# kaaEmonitor_2v0.net
KiCad netlist of a schematic drawn in EAGLE
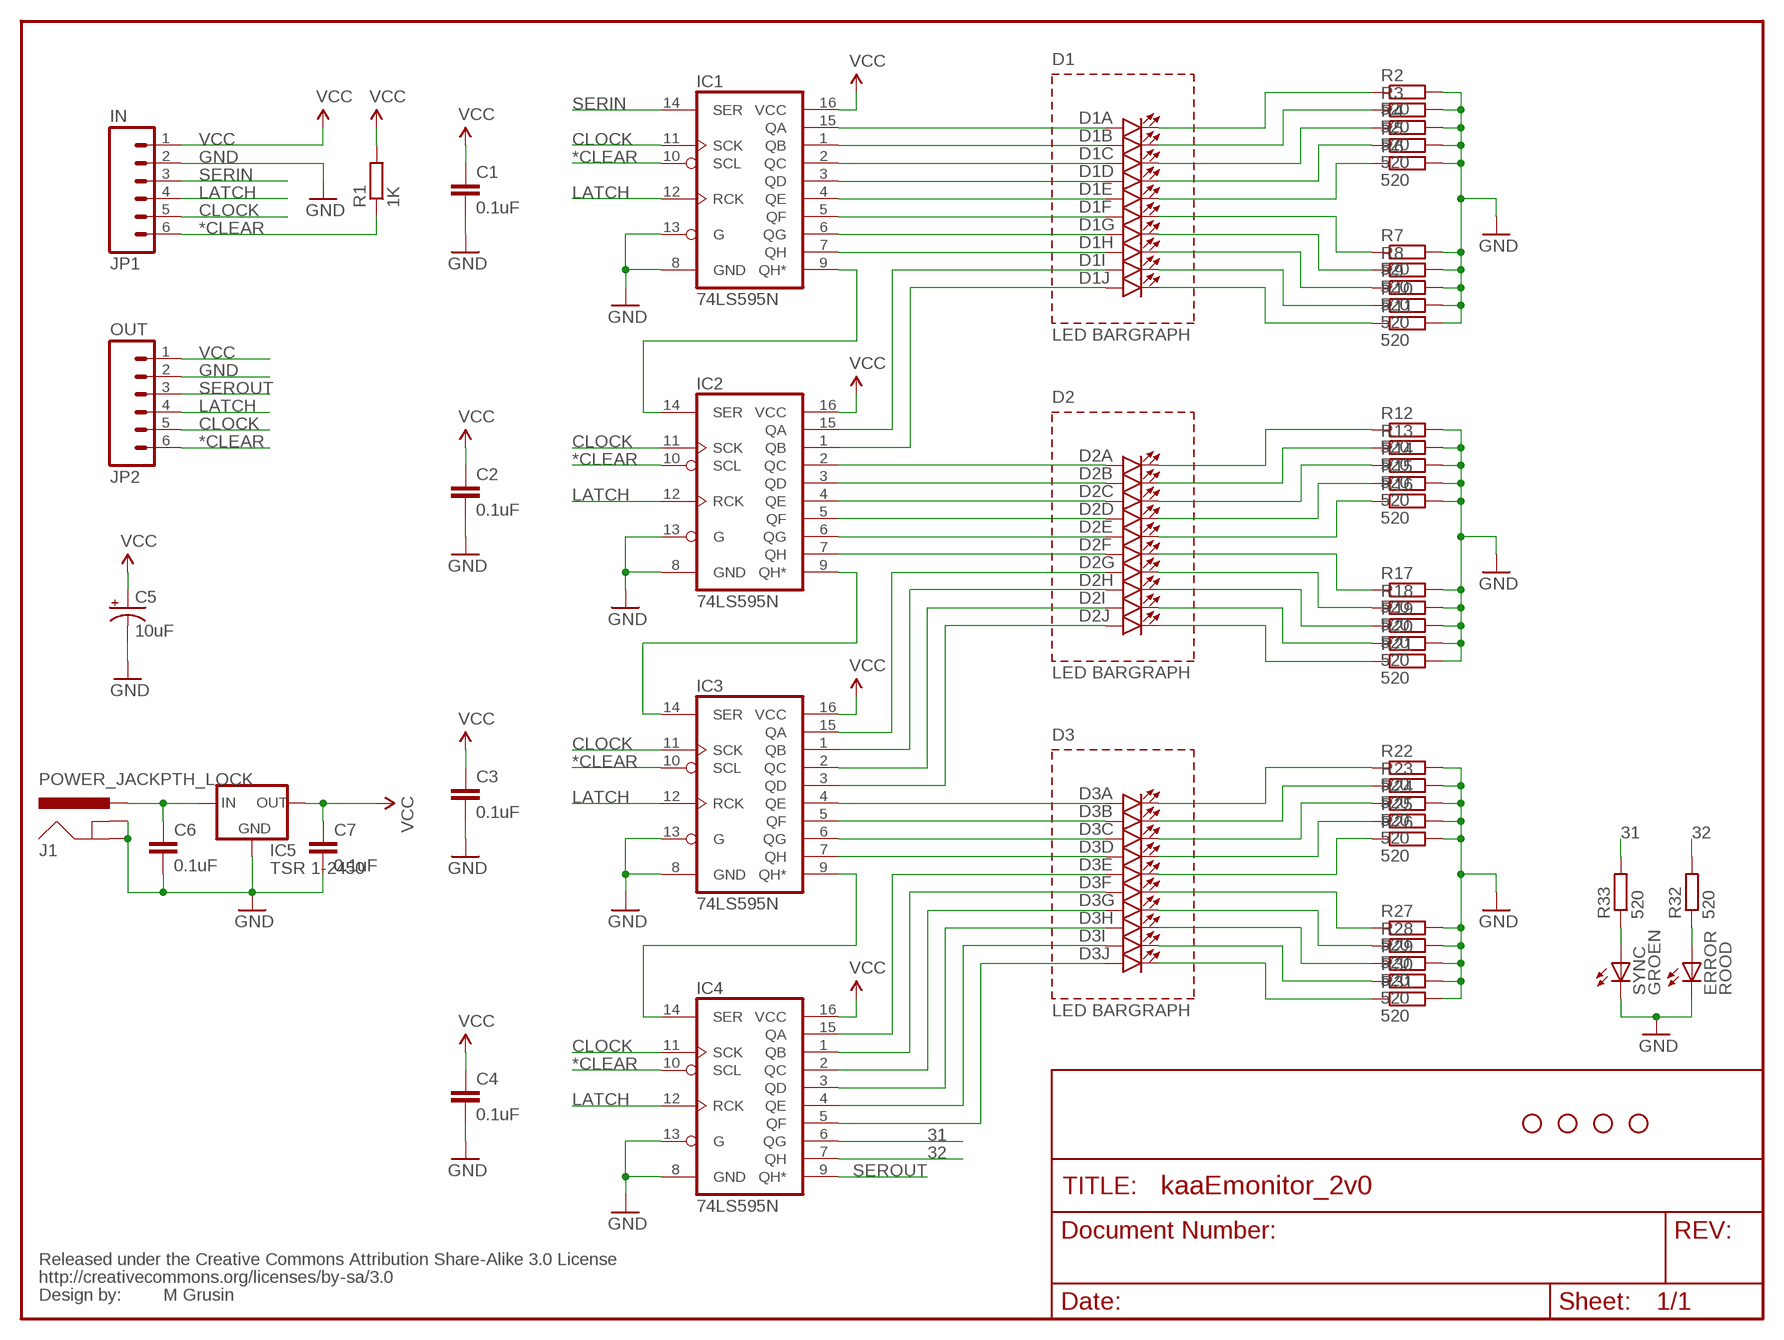
[diagram p0: schematic, sheet 1]

(export (version "E")
  (design (tool "Eeschema 10.0.6"))
  (components
    (comp (ref "C1")
      (value "0.1uF")
      (footprint "eagle-import:CAP-PTH-SMALL2")
      (libsource (lib "eagle-import") (part "CAPPTH2"))
    )
    (comp (ref "C2")
      (value "0.1uF")
      (footprint "eagle-import:CAP-PTH-SMALL2")
      (libsource (lib "eagle-import") (part "CAPPTH2"))
    )
    (comp (ref "C3")
      (value "0.1uF")
      (footprint "eagle-import:CAP-PTH-SMALL2")
      (libsource (lib "eagle-import") (part "CAPPTH2"))
    )
    (comp (ref "C4")
      (value "0.1uF")
      (footprint "eagle-import:CAP-PTH-SMALL2")
      (libsource (lib "eagle-import") (part "CAPPTH2"))
    )
    (comp (ref "C5")
      (value "10uF")
      (footprint "eagle-import:CPOL-RADIAL-10UF-25V")
      (libsource (lib "eagle-import") (part "CAP_POLPTH2"))
    )
    (comp (ref "C6")
      (value "0.1uF")
      (footprint "eagle-import:CAP-PTH-SMALL2")
      (libsource (lib "eagle-import") (part "CAPPTH2"))
    )
    (comp (ref "C7")
      (value "0.1uF")
      (footprint "eagle-import:CAP-PTH-SMALL2")
      (libsource (lib "eagle-import") (part "CAPPTH2"))
    )
    (comp (ref "D1")
      (value "LED_BARGRAPH_10")
      (footprint "eagle-import:LED_BARGAPH_10")
      (libsource (lib "eagle-import") (part "LED_BARGRAPH_10"))
    )
    (comp (ref "D2")
      (value "LED_BARGRAPH_10")
      (footprint "eagle-import:LED_BARGAPH_10")
      (libsource (lib "eagle-import") (part "LED_BARGRAPH_10"))
    )
    (comp (ref "D3")
      (value "LED_BARGRAPH_10")
      (footprint "eagle-import:LED_BARGAPH_10")
      (libsource (lib "eagle-import") (part "LED_BARGRAPH_10"))
    )
    (comp (ref "ERROR")
      (value "ROOD")
      (footprint "eagle-import:LED3MM")
      (libsource (lib "eagle-import") (part "LED3MM"))
    )
    (comp (ref "IC1")
      (value "74LS595N")
      (footprint "eagle-import:DIL16")
      (libsource (lib "eagle-import") (part "74595NLS"))
    )
    (comp (ref "IC2")
      (value "74LS595N")
      (footprint "eagle-import:DIL16")
      (libsource (lib "eagle-import") (part "74595NLS"))
    )
    (comp (ref "IC3")
      (value "74LS595N")
      (footprint "eagle-import:DIL16")
      (libsource (lib "eagle-import") (part "74595NLS"))
    )
    (comp (ref "IC4")
      (value "74LS595N")
      (footprint "eagle-import:DIL16")
      (libsource (lib "eagle-import") (part "74595NLS"))
    )
    (comp (ref "IC5")
      (value "TSR 1-2450")
      (footprint "eagle-import:TO220-IGO")
      (libsource (lib "eagle-import") (part "V_REG_78XXSINK"))
    )
    (comp (ref "J1")
      (value "POWER_JACKPTH_LOCK")
      (footprint "eagle-import:POWER_JACK_PTH_LOCK")
      (libsource (lib "eagle-import") (part "POWER_JACKPTH_LOCK"))
    )
    (comp (ref "JP1")
      (value "IN")
      (footprint "eagle-import:1X06")
      (libsource (lib "eagle-import") (part "M06SIP"))
    )
    (comp (ref "JP2")
      (value "OUT")
      (footprint "eagle-import:1X06")
      (libsource (lib "eagle-import") (part "M06SIP"))
    )
    (comp (ref "R1")
      (value "1K")
      (footprint "eagle-import:0204_5")
      (libsource (lib "eagle-import") (part "R-EU_0204/5"))
    )
    (comp (ref "R2")
      (value "520")
      (footprint "eagle-import:0204_5")
      (libsource (lib "eagle-import") (part "R-EU_0204/5"))
    )
    (comp (ref "R3")
      (value "520")
      (footprint "eagle-import:0204_5")
      (libsource (lib "eagle-import") (part "R-EU_0204/5"))
    )
    (comp (ref "R4")
      (value "520")
      (footprint "eagle-import:0204_5")
      (libsource (lib "eagle-import") (part "R-EU_0204/5"))
    )
    (comp (ref "R5")
      (value "520")
      (footprint "eagle-import:0204_5")
      (libsource (lib "eagle-import") (part "R-EU_0204/5"))
    )
    (comp (ref "R6")
      (value "520")
      (footprint "eagle-import:0204_5")
      (libsource (lib "eagle-import") (part "R-EU_0204/5"))
    )
    (comp (ref "R7")
      (value "520")
      (footprint "eagle-import:0204_5")
      (libsource (lib "eagle-import") (part "R-EU_0204/5"))
    )
    (comp (ref "R8")
      (value "520")
      (footprint "eagle-import:0204_5")
      (libsource (lib "eagle-import") (part "R-EU_0204/5"))
    )
    (comp (ref "R9")
      (value "520")
      (footprint "eagle-import:0204_5")
      (libsource (lib "eagle-import") (part "R-EU_0204/5"))
    )
    (comp (ref "R10")
      (value "520")
      (footprint "eagle-import:0204_5")
      (libsource (lib "eagle-import") (part "R-EU_0204/5"))
    )
    (comp (ref "R11")
      (value "520")
      (footprint "eagle-import:0204_5")
      (libsource (lib "eagle-import") (part "R-EU_0204/5"))
    )
    (comp (ref "R12")
      (value "520")
      (footprint "eagle-import:0204_5")
      (libsource (lib "eagle-import") (part "R-EU_0204/5"))
    )
    (comp (ref "R13")
      (value "520")
      (footprint "eagle-import:0204_5")
      (libsource (lib "eagle-import") (part "R-EU_0204/5"))
    )
    (comp (ref "R14")
      (value "520")
      (footprint "eagle-import:0204_5")
      (libsource (lib "eagle-import") (part "R-EU_0204/5"))
    )
    (comp (ref "R15")
      (value "520")
      (footprint "eagle-import:0204_5")
      (libsource (lib "eagle-import") (part "R-EU_0204/5"))
    )
    (comp (ref "R16")
      (value "520")
      (footprint "eagle-import:0204_5")
      (libsource (lib "eagle-import") (part "R-EU_0204/5"))
    )
    (comp (ref "R17")
      (value "520")
      (footprint "eagle-import:0204_5")
      (libsource (lib "eagle-import") (part "R-EU_0204/5"))
    )
    (comp (ref "R18")
      (value "520")
      (footprint "eagle-import:0204_5")
      (libsource (lib "eagle-import") (part "R-EU_0204/5"))
    )
    (comp (ref "R19")
      (value "520")
      (footprint "eagle-import:0204_5")
      (libsource (lib "eagle-import") (part "R-EU_0204/5"))
    )
    (comp (ref "R20")
      (value "520")
      (footprint "eagle-import:0204_5")
      (libsource (lib "eagle-import") (part "R-EU_0204/5"))
    )
    (comp (ref "R21")
      (value "520")
      (footprint "eagle-import:0204_5")
      (libsource (lib "eagle-import") (part "R-EU_0204/5"))
    )
    (comp (ref "R22")
      (value "520")
      (footprint "eagle-import:0204_5")
      (libsource (lib "eagle-import") (part "R-EU_0204/5"))
    )
    (comp (ref "R23")
      (value "520")
      (footprint "eagle-import:0204_5")
      (libsource (lib "eagle-import") (part "R-EU_0204/5"))
    )
    (comp (ref "R24")
      (value "520")
      (footprint "eagle-import:0204_5")
      (libsource (lib "eagle-import") (part "R-EU_0204/5"))
    )
    (comp (ref "R25")
      (value "520")
      (footprint "eagle-import:0204_5")
      (libsource (lib "eagle-import") (part "R-EU_0204/5"))
    )
    (comp (ref "R26")
      (value "520")
      (footprint "eagle-import:0204_5")
      (libsource (lib "eagle-import") (part "R-EU_0204/5"))
    )
    (comp (ref "R27")
      (value "520")
      (footprint "eagle-import:0204_5")
      (libsource (lib "eagle-import") (part "R-EU_0204/5"))
    )
    (comp (ref "R28")
      (value "520")
      (footprint "eagle-import:0204_5")
      (libsource (lib "eagle-import") (part "R-EU_0204/5"))
    )
    (comp (ref "R29")
      (value "520")
      (footprint "eagle-import:0204_5")
      (libsource (lib "eagle-import") (part "R-EU_0204/5"))
    )
    (comp (ref "R30")
      (value "520")
      (footprint "eagle-import:0204_5")
      (libsource (lib "eagle-import") (part "R-EU_0204/5"))
    )
    (comp (ref "R31")
      (value "520")
      (footprint "eagle-import:0204_5")
      (libsource (lib "eagle-import") (part "R-EU_0204/5"))
    )
    (comp (ref "R32")
      (value "520")
      (footprint "eagle-import:0204_5")
      (libsource (lib "eagle-import") (part "R-EU_0204/5"))
    )
    (comp (ref "R33")
      (value "520")
      (footprint "eagle-import:0204_5")
      (libsource (lib "eagle-import") (part "R-EU_0204/5"))
    )
    (comp (ref "SO1")
      (value "STAND-OFF")
      (footprint "eagle-import:STAND-OFF")
      (libsource (lib "eagle-import") (part "STAND-OFF"))
    )
    (comp (ref "SO2")
      (value "STAND-OFF")
      (footprint "eagle-import:STAND-OFF")
      (libsource (lib "eagle-import") (part "STAND-OFF"))
    )
    (comp (ref "SO3")
      (value "STAND-OFF")
      (footprint "eagle-import:STAND-OFF")
      (libsource (lib "eagle-import") (part "STAND-OFF"))
    )
    (comp (ref "SO4")
      (value "STAND-OFF")
      (footprint "eagle-import:STAND-OFF")
      (libsource (lib "eagle-import") (part "STAND-OFF"))
    )
    (comp (ref "SYNC")
      (value "GROEN")
      (footprint "eagle-import:LED3MM")
      (libsource (lib "eagle-import") (part "LED3MM"))
    )
    (comp (ref "U$6")
      (value "CREATIVE_COMMONS")
      (footprint "eagle-import:CREATIVE_COMMONS")
      (libsource (lib "eagle-import") (part "CREATIVE_COMMONS"))
    )
  )
  (nets
    (net (code "1") (name "/*CLEAR") (class "Default")
      (node (ref "IC1") (pin "10") (pinfunction "SCL_10") (pintype "input"))
      (node (ref "IC2") (pin "10") (pinfunction "SCL_10") (pintype "input"))
      (node (ref "IC3") (pin "10") (pinfunction "SCL_10") (pintype "input"))
      (node (ref "IC4") (pin "10") (pinfunction "SCL_10") (pintype "input"))
      (node (ref "JP1") (pin "6") (pinfunction "6_6") (pintype "passive"))
      (node (ref "JP2") (pin "6") (pinfunction "6_6") (pintype "passive"))
      (node (ref "R1") (pin "1") (pinfunction "1_1") (pintype "passive"))
    )
    (net (code "2") (name "/31") (class "Default")
      (node (ref "IC4") (pin "6") (pinfunction "QG_6") (pintype "tri_state"))
      (node (ref "R33") (pin "2") (pinfunction "2_2") (pintype "passive"))
    )
    (net (code "3") (name "/32") (class "Default")
      (node (ref "IC4") (pin "7") (pinfunction "QH_7") (pintype "tri_state"))
      (node (ref "R32") (pin "2") (pinfunction "2_2") (pintype "passive"))
    )
    (net (code "4") (name "/CLOCK") (class "Default")
      (node (ref "IC1") (pin "11") (pinfunction "SCK_11") (pintype "input"))
      (node (ref "IC2") (pin "11") (pinfunction "SCK_11") (pintype "input"))
      (node (ref "IC3") (pin "11") (pinfunction "SCK_11") (pintype "input"))
      (node (ref "IC4") (pin "11") (pinfunction "SCK_11") (pintype "input"))
      (node (ref "JP1") (pin "5") (pinfunction "5_5") (pintype "passive"))
      (node (ref "JP2") (pin "5") (pinfunction "5_5") (pintype "passive"))
    )
    (net (code "5") (name "/LATCH") (class "Default")
      (node (ref "IC1") (pin "12") (pinfunction "RCK_12") (pintype "input"))
      (node (ref "IC2") (pin "12") (pinfunction "RCK_12") (pintype "input"))
      (node (ref "IC3") (pin "12") (pinfunction "RCK_12") (pintype "input"))
      (node (ref "IC4") (pin "12") (pinfunction "RCK_12") (pintype "input"))
      (node (ref "JP1") (pin "4") (pinfunction "4_4") (pintype "passive"))
      (node (ref "JP2") (pin "4") (pinfunction "4_4") (pintype "passive"))
    )
    (net (code "6") (name "/SERIN") (class "Default")
      (node (ref "IC1") (pin "14") (pinfunction "SER_14") (pintype "input"))
      (node (ref "JP1") (pin "3") (pinfunction "3_3") (pintype "passive"))
    )
    (net (code "7") (name "/SEROUT") (class "Default")
      (node (ref "IC4") (pin "9") (pinfunction "QH*_9") (pintype "tri_state"))
      (node (ref "JP2") (pin "3") (pinfunction "3_3") (pintype "passive"))
    )
    (net (code "8") (name "GND") (class "Default")
      (node (ref "C1") (pin "2") (pinfunction "2_2") (pintype "passive"))
      (node (ref "C2") (pin "2") (pinfunction "2_2") (pintype "passive"))
      (node (ref "C3") (pin "2") (pinfunction "2_2") (pintype "passive"))
      (node (ref "C4") (pin "2") (pinfunction "2_2") (pintype "passive"))
      (node (ref "C5") (pin "2") (pinfunction "-_2") (pintype "passive"))
      (node (ref "C6") (pin "2") (pinfunction "2_2") (pintype "passive"))
      (node (ref "C7") (pin "2") (pinfunction "2_2") (pintype "passive"))
      (node (ref "ERROR") (pin "K") (pinfunction "C_K") (pintype "passive"))
      (node (ref "IC1") (pin "13") (pinfunction "G_13") (pintype "input"))
      (node (ref "IC1") (pin "8") (pinfunction "GND_8") (pintype "power_in"))
      (node (ref "IC2") (pin "13") (pinfunction "G_13") (pintype "input"))
      (node (ref "IC2") (pin "8") (pinfunction "GND_8") (pintype "power_in"))
      (node (ref "IC3") (pin "13") (pinfunction "G_13") (pintype "input"))
      (node (ref "IC3") (pin "8") (pinfunction "GND_8") (pintype "power_in"))
      (node (ref "IC4") (pin "13") (pinfunction "G_13") (pintype "input"))
      (node (ref "IC4") (pin "8") (pinfunction "GND_8") (pintype "power_in"))
      (node (ref "IC5") (pin "GND") (pinfunction "GND_GND") (pintype "input"))
      (node (ref "J1") (pin "GND") (pinfunction "GND_GND") (pintype "bidirectional"))
      (node (ref "J1") (pin "GNDBREAK") (pinfunction "GNDBREAK_GNDBREAK") (pintype "bidirectional"))
      (node (ref "JP1") (pin "2") (pinfunction "2_2") (pintype "passive"))
      (node (ref "JP2") (pin "2") (pinfunction "2_2") (pintype "passive"))
      (node (ref "R10") (pin "2") (pinfunction "2_2") (pintype "passive"))
      (node (ref "R11") (pin "2") (pinfunction "2_2") (pintype "passive"))
      (node (ref "R12") (pin "2") (pinfunction "2_2") (pintype "passive"))
      (node (ref "R13") (pin "2") (pinfunction "2_2") (pintype "passive"))
      (node (ref "R14") (pin "2") (pinfunction "2_2") (pintype "passive"))
      (node (ref "R15") (pin "2") (pinfunction "2_2") (pintype "passive"))
      (node (ref "R16") (pin "2") (pinfunction "2_2") (pintype "passive"))
      (node (ref "R17") (pin "2") (pinfunction "2_2") (pintype "passive"))
      (node (ref "R18") (pin "2") (pinfunction "2_2") (pintype "passive"))
      (node (ref "R19") (pin "2") (pinfunction "2_2") (pintype "passive"))
      (node (ref "R2") (pin "2") (pinfunction "2_2") (pintype "passive"))
      (node (ref "R20") (pin "2") (pinfunction "2_2") (pintype "passive"))
      (node (ref "R21") (pin "2") (pinfunction "2_2") (pintype "passive"))
      (node (ref "R22") (pin "2") (pinfunction "2_2") (pintype "passive"))
      (node (ref "R23") (pin "2") (pinfunction "2_2") (pintype "passive"))
      (node (ref "R24") (pin "2") (pinfunction "2_2") (pintype "passive"))
      (node (ref "R25") (pin "2") (pinfunction "2_2") (pintype "passive"))
      (node (ref "R26") (pin "2") (pinfunction "2_2") (pintype "passive"))
      (node (ref "R27") (pin "2") (pinfunction "2_2") (pintype "passive"))
      (node (ref "R28") (pin "2") (pinfunction "2_2") (pintype "passive"))
      (node (ref "R29") (pin "2") (pinfunction "2_2") (pintype "passive"))
      (node (ref "R3") (pin "2") (pinfunction "2_2") (pintype "passive"))
      (node (ref "R30") (pin "2") (pinfunction "2_2") (pintype "passive"))
      (node (ref "R31") (pin "2") (pinfunction "2_2") (pintype "passive"))
      (node (ref "R4") (pin "2") (pinfunction "2_2") (pintype "passive"))
      (node (ref "R5") (pin "2") (pinfunction "2_2") (pintype "passive"))
      (node (ref "R6") (pin "2") (pinfunction "2_2") (pintype "passive"))
      (node (ref "R7") (pin "2") (pinfunction "2_2") (pintype "passive"))
      (node (ref "R8") (pin "2") (pinfunction "2_2") (pintype "passive"))
      (node (ref "R9") (pin "2") (pinfunction "2_2") (pintype "passive"))
      (node (ref "SYNC") (pin "K") (pinfunction "C_K") (pintype "passive"))
    )
    (net (code "9") (name "Net-(C6-Pad1)") (class "Default")
      (node (ref "C6") (pin "1") (pinfunction "1_1") (pintype "passive"))
      (node (ref "IC5") (pin "IN") (pinfunction "IN_IN") (pintype "input"))
      (node (ref "J1") (pin "PWR") (pinfunction "PWR_PWR") (pintype "bidirectional"))
    )
    (net (code "10") (name "Net-(D1A-A)") (class "Default")
      (node (ref "D1") (pin "1") (pinfunction "A_1") (pintype "passive"))
      (node (ref "IC1") (pin "15") (pinfunction "QA_15") (pintype "tri_state"))
    )
    (net (code "11") (name "Net-(D1A-C)") (class "Default")
      (node (ref "D1") (pin "20") (pinfunction "C_20") (pintype "passive"))
      (node (ref "R2") (pin "1") (pinfunction "1_1") (pintype "passive"))
    )
    (net (code "12") (name "Net-(D1B-A)") (class "Default")
      (node (ref "D1") (pin "2") (pinfunction "A_2") (pintype "passive"))
      (node (ref "IC1") (pin "1") (pinfunction "QB_1") (pintype "tri_state"))
    )
    (net (code "13") (name "Net-(D1B-C)") (class "Default")
      (node (ref "D1") (pin "19") (pinfunction "C_19") (pintype "passive"))
      (node (ref "R3") (pin "1") (pinfunction "1_1") (pintype "passive"))
    )
    (net (code "14") (name "Net-(D1C-A)") (class "Default")
      (node (ref "D1") (pin "3") (pinfunction "A_3") (pintype "passive"))
      (node (ref "IC1") (pin "2") (pinfunction "QC_2") (pintype "tri_state"))
    )
    (net (code "15") (name "Net-(D1C-C)") (class "Default")
      (node (ref "D1") (pin "18") (pinfunction "C_18") (pintype "passive"))
      (node (ref "R4") (pin "1") (pinfunction "1_1") (pintype "passive"))
    )
    (net (code "16") (name "Net-(D1D-A)") (class "Default")
      (node (ref "D1") (pin "4") (pinfunction "A_4") (pintype "passive"))
      (node (ref "IC1") (pin "3") (pinfunction "QD_3") (pintype "tri_state"))
    )
    (net (code "17") (name "Net-(D1D-C)") (class "Default")
      (node (ref "D1") (pin "17") (pinfunction "C_17") (pintype "passive"))
      (node (ref "R5") (pin "1") (pinfunction "1_1") (pintype "passive"))
    )
    (net (code "18") (name "Net-(D1E-A)") (class "Default")
      (node (ref "D1") (pin "5") (pinfunction "A_5") (pintype "passive"))
      (node (ref "IC1") (pin "4") (pinfunction "QE_4") (pintype "tri_state"))
    )
    (net (code "19") (name "Net-(D1E-C)") (class "Default")
      (node (ref "D1") (pin "16") (pinfunction "C_16") (pintype "passive"))
      (node (ref "R6") (pin "1") (pinfunction "1_1") (pintype "passive"))
    )
    (net (code "20") (name "Net-(D1F-A)") (class "Default")
      (node (ref "D1") (pin "6") (pinfunction "A_6") (pintype "passive"))
      (node (ref "IC1") (pin "5") (pinfunction "QF_5") (pintype "tri_state"))
    )
    (net (code "21") (name "Net-(D1F-C)") (class "Default")
      (node (ref "D1") (pin "15") (pinfunction "C_15") (pintype "passive"))
      (node (ref "R7") (pin "1") (pinfunction "1_1") (pintype "passive"))
    )
    (net (code "22") (name "Net-(D1G-A)") (class "Default")
      (node (ref "D1") (pin "7") (pinfunction "A_7") (pintype "passive"))
      (node (ref "IC1") (pin "6") (pinfunction "QG_6") (pintype "tri_state"))
    )
    (net (code "23") (name "Net-(D1G-C)") (class "Default")
      (node (ref "D1") (pin "14") (pinfunction "C_14") (pintype "passive"))
      (node (ref "R8") (pin "1") (pinfunction "1_1") (pintype "passive"))
    )
    (net (code "24") (name "Net-(D1H-A)") (class "Default")
      (node (ref "D1") (pin "8") (pinfunction "A_8") (pintype "passive"))
      (node (ref "IC1") (pin "7") (pinfunction "QH_7") (pintype "tri_state"))
    )
    (net (code "25") (name "Net-(D1H-C)") (class "Default")
      (node (ref "D1") (pin "13") (pinfunction "C_13") (pintype "passive"))
      (node (ref "R9") (pin "1") (pinfunction "1_1") (pintype "passive"))
    )
    (net (code "26") (name "Net-(D1I-A)") (class "Default")
      (node (ref "D1") (pin "9") (pinfunction "A_9") (pintype "passive"))
      (node (ref "IC2") (pin "15") (pinfunction "QA_15") (pintype "tri_state"))
    )
    (net (code "27") (name "Net-(D1I-C)") (class "Default")
      (node (ref "D1") (pin "12") (pinfunction "C_12") (pintype "passive"))
      (node (ref "R10") (pin "1") (pinfunction "1_1") (pintype "passive"))
    )
    (net (code "28") (name "Net-(D1J-A)") (class "Default")
      (node (ref "D1") (pin "10") (pinfunction "A_10") (pintype "passive"))
      (node (ref "IC2") (pin "1") (pinfunction "QB_1") (pintype "tri_state"))
    )
    (net (code "29") (name "Net-(D1J-C)") (class "Default")
      (node (ref "D1") (pin "11") (pinfunction "C_11") (pintype "passive"))
      (node (ref "R11") (pin "1") (pinfunction "1_1") (pintype "passive"))
    )
    (net (code "30") (name "Net-(D2A-A)") (class "Default")
      (node (ref "D2") (pin "1") (pinfunction "A_1") (pintype "passive"))
      (node (ref "IC2") (pin "2") (pinfunction "QC_2") (pintype "tri_state"))
    )
    (net (code "31") (name "Net-(D2A-C)") (class "Default")
      (node (ref "D2") (pin "20") (pinfunction "C_20") (pintype "passive"))
      (node (ref "R12") (pin "1") (pinfunction "1_1") (pintype "passive"))
    )
    (net (code "32") (name "Net-(D2B-A)") (class "Default")
      (node (ref "D2") (pin "2") (pinfunction "A_2") (pintype "passive"))
      (node (ref "IC2") (pin "3") (pinfunction "QD_3") (pintype "tri_state"))
    )
    (net (code "33") (name "Net-(D2B-C)") (class "Default")
      (node (ref "D2") (pin "19") (pinfunction "C_19") (pintype "passive"))
      (node (ref "R13") (pin "1") (pinfunction "1_1") (pintype "passive"))
    )
    (net (code "34") (name "Net-(D2C-A)") (class "Default")
      (node (ref "D2") (pin "3") (pinfunction "A_3") (pintype "passive"))
      (node (ref "IC2") (pin "4") (pinfunction "QE_4") (pintype "tri_state"))
    )
    (net (code "35") (name "Net-(D2C-C)") (class "Default")
      (node (ref "D2") (pin "18") (pinfunction "C_18") (pintype "passive"))
      (node (ref "R14") (pin "1") (pinfunction "1_1") (pintype "passive"))
    )
    (net (code "36") (name "Net-(D2D-A)") (class "Default")
      (node (ref "D2") (pin "4") (pinfunction "A_4") (pintype "passive"))
      (node (ref "IC2") (pin "5") (pinfunction "QF_5") (pintype "tri_state"))
    )
    (net (code "37") (name "Net-(D2D-C)") (class "Default")
      (node (ref "D2") (pin "17") (pinfunction "C_17") (pintype "passive"))
      (node (ref "R15") (pin "1") (pinfunction "1_1") (pintype "passive"))
    )
    (net (code "38") (name "Net-(D2E-A)") (class "Default")
      (node (ref "D2") (pin "5") (pinfunction "A_5") (pintype "passive"))
      (node (ref "IC2") (pin "6") (pinfunction "QG_6") (pintype "tri_state"))
    )
    (net (code "39") (name "Net-(D2E-C)") (class "Default")
      (node (ref "D2") (pin "16") (pinfunction "C_16") (pintype "passive"))
      (node (ref "R16") (pin "1") (pinfunction "1_1") (pintype "passive"))
    )
    (net (code "40") (name "Net-(D2F-A)") (class "Default")
      (node (ref "D2") (pin "6") (pinfunction "A_6") (pintype "passive"))
      (node (ref "IC2") (pin "7") (pinfunction "QH_7") (pintype "tri_state"))
    )
    (net (code "41") (name "Net-(D2F-C)") (class "Default")
      (node (ref "D2") (pin "15") (pinfunction "C_15") (pintype "passive"))
      (node (ref "R17") (pin "1") (pinfunction "1_1") (pintype "passive"))
    )
    (net (code "42") (name "Net-(D2G-A)") (class "Default")
      (node (ref "D2") (pin "7") (pinfunction "A_7") (pintype "passive"))
      (node (ref "IC3") (pin "15") (pinfunction "QA_15") (pintype "tri_state"))
    )
    (net (code "43") (name "Net-(D2G-C)") (class "Default")
      (node (ref "D2") (pin "14") (pinfunction "C_14") (pintype "passive"))
      (node (ref "R18") (pin "1") (pinfunction "1_1") (pintype "passive"))
    )
    (net (code "44") (name "Net-(D2H-A)") (class "Default")
      (node (ref "D2") (pin "8") (pinfunction "A_8") (pintype "passive"))
      (node (ref "IC3") (pin "1") (pinfunction "QB_1") (pintype "tri_state"))
    )
    (net (code "45") (name "Net-(D2H-C)") (class "Default")
      (node (ref "D2") (pin "13") (pinfunction "C_13") (pintype "passive"))
      (node (ref "R19") (pin "1") (pinfunction "1_1") (pintype "passive"))
    )
    (net (code "46") (name "Net-(D2I-A)") (class "Default")
      (node (ref "D2") (pin "9") (pinfunction "A_9") (pintype "passive"))
      (node (ref "IC3") (pin "2") (pinfunction "QC_2") (pintype "tri_state"))
    )
    (net (code "47") (name "Net-(D2I-C)") (class "Default")
      (node (ref "D2") (pin "12") (pinfunction "C_12") (pintype "passive"))
      (node (ref "R20") (pin "1") (pinfunction "1_1") (pintype "passive"))
    )
    (net (code "48") (name "Net-(D2J-A)") (class "Default")
      (node (ref "D2") (pin "10") (pinfunction "A_10") (pintype "passive"))
      (node (ref "IC3") (pin "3") (pinfunction "QD_3") (pintype "tri_state"))
    )
    (net (code "49") (name "Net-(D2J-C)") (class "Default")
      (node (ref "D2") (pin "11") (pinfunction "C_11") (pintype "passive"))
      (node (ref "R21") (pin "1") (pinfunction "1_1") (pintype "passive"))
    )
    (net (code "50") (name "Net-(D3A-A)") (class "Default")
      (node (ref "D3") (pin "1") (pinfunction "A_1") (pintype "passive"))
      (node (ref "IC3") (pin "4") (pinfunction "QE_4") (pintype "tri_state"))
    )
    (net (code "51") (name "Net-(D3A-C)") (class "Default")
      (node (ref "D3") (pin "20") (pinfunction "C_20") (pintype "passive"))
      (node (ref "R22") (pin "1") (pinfunction "1_1") (pintype "passive"))
    )
    (net (code "52") (name "Net-(D3B-A)") (class "Default")
      (node (ref "D3") (pin "2") (pinfunction "A_2") (pintype "passive"))
      (node (ref "IC3") (pin "5") (pinfunction "QF_5") (pintype "tri_state"))
    )
    (net (code "53") (name "Net-(D3B-C)") (class "Default")
      (node (ref "D3") (pin "19") (pinfunction "C_19") (pintype "passive"))
      (node (ref "R23") (pin "1") (pinfunction "1_1") (pintype "passive"))
    )
    (net (code "54") (name "Net-(D3C-A)") (class "Default")
      (node (ref "D3") (pin "3") (pinfunction "A_3") (pintype "passive"))
      (node (ref "IC3") (pin "6") (pinfunction "QG_6") (pintype "tri_state"))
    )
    (net (code "55") (name "Net-(D3C-C)") (class "Default")
      (node (ref "D3") (pin "18") (pinfunction "C_18") (pintype "passive"))
      (node (ref "R24") (pin "1") (pinfunction "1_1") (pintype "passive"))
    )
    (net (code "56") (name "Net-(D3D-A)") (class "Default")
      (node (ref "D3") (pin "4") (pinfunction "A_4") (pintype "passive"))
      (node (ref "IC3") (pin "7") (pinfunction "QH_7") (pintype "tri_state"))
    )
    (net (code "57") (name "Net-(D3D-C)") (class "Default")
      (node (ref "D3") (pin "17") (pinfunction "C_17") (pintype "passive"))
      (node (ref "R25") (pin "1") (pinfunction "1_1") (pintype "passive"))
    )
    (net (code "58") (name "Net-(D3E-A)") (class "Default")
      (node (ref "D3") (pin "5") (pinfunction "A_5") (pintype "passive"))
      (node (ref "IC4") (pin "15") (pinfunction "QA_15") (pintype "tri_state"))
    )
    (net (code "59") (name "Net-(D3E-C)") (class "Default")
      (node (ref "D3") (pin "16") (pinfunction "C_16") (pintype "passive"))
      (node (ref "R26") (pin "1") (pinfunction "1_1") (pintype "passive"))
    )
    (net (code "60") (name "Net-(D3F-A)") (class "Default")
      (node (ref "D3") (pin "6") (pinfunction "A_6") (pintype "passive"))
      (node (ref "IC4") (pin "1") (pinfunction "QB_1") (pintype "tri_state"))
    )
    (net (code "61") (name "Net-(D3F-C)") (class "Default")
      (node (ref "D3") (pin "15") (pinfunction "C_15") (pintype "passive"))
      (node (ref "R27") (pin "1") (pinfunction "1_1") (pintype "passive"))
    )
    (net (code "62") (name "Net-(D3G-A)") (class "Default")
      (node (ref "D3") (pin "7") (pinfunction "A_7") (pintype "passive"))
      (node (ref "IC4") (pin "2") (pinfunction "QC_2") (pintype "tri_state"))
    )
    (net (code "63") (name "Net-(D3G-C)") (class "Default")
      (node (ref "D3") (pin "14") (pinfunction "C_14") (pintype "passive"))
      (node (ref "R28") (pin "1") (pinfunction "1_1") (pintype "passive"))
    )
    (net (code "64") (name "Net-(D3H-A)") (class "Default")
      (node (ref "D3") (pin "8") (pinfunction "A_8") (pintype "passive"))
      (node (ref "IC4") (pin "3") (pinfunction "QD_3") (pintype "tri_state"))
    )
    (net (code "65") (name "Net-(D3H-C)") (class "Default")
      (node (ref "D3") (pin "13") (pinfunction "C_13") (pintype "passive"))
      (node (ref "R29") (pin "1") (pinfunction "1_1") (pintype "passive"))
    )
    (net (code "66") (name "Net-(D3I-A)") (class "Default")
      (node (ref "D3") (pin "9") (pinfunction "A_9") (pintype "passive"))
      (node (ref "IC4") (pin "4") (pinfunction "QE_4") (pintype "tri_state"))
    )
    (net (code "67") (name "Net-(D3I-C)") (class "Default")
      (node (ref "D3") (pin "12") (pinfunction "C_12") (pintype "passive"))
      (node (ref "R30") (pin "1") (pinfunction "1_1") (pintype "passive"))
    )
    (net (code "68") (name "Net-(D3J-A)") (class "Default")
      (node (ref "D3") (pin "10") (pinfunction "A_10") (pintype "passive"))
      (node (ref "IC4") (pin "5") (pinfunction "QF_5") (pintype "tri_state"))
    )
    (net (code "69") (name "Net-(D3J-C)") (class "Default")
      (node (ref "D3") (pin "11") (pinfunction "C_11") (pintype "passive"))
      (node (ref "R31") (pin "1") (pinfunction "1_1") (pintype "passive"))
    )
    (net (code "70") (name "Net-(ERROR-PadA)") (class "Default")
      (node (ref "ERROR") (pin "A") (pinfunction "A_A") (pintype "passive"))
      (node (ref "R32") (pin "1") (pinfunction "1_1") (pintype "passive"))
    )
    (net (code "71") (name "Net-(IC1-QH*)") (class "Default")
      (node (ref "IC1") (pin "9") (pinfunction "QH*_9") (pintype "tri_state"))
      (node (ref "IC2") (pin "14") (pinfunction "SER_14") (pintype "input"))
    )
    (net (code "72") (name "Net-(IC2-QH*)") (class "Default")
      (node (ref "IC2") (pin "9") (pinfunction "QH*_9") (pintype "tri_state"))
      (node (ref "IC3") (pin "14") (pinfunction "SER_14") (pintype "input"))
    )
    (net (code "73") (name "Net-(IC3-QH*)") (class "Default")
      (node (ref "IC3") (pin "9") (pinfunction "QH*_9") (pintype "tri_state"))
      (node (ref "IC4") (pin "14") (pinfunction "SER_14") (pintype "input"))
    )
    (net (code "74") (name "Net-(R33-Pad1)") (class "Default")
      (node (ref "R33") (pin "1") (pinfunction "1_1") (pintype "passive"))
      (node (ref "SYNC") (pin "A") (pinfunction "A_A") (pintype "passive"))
    )
    (net (code "75") (name "VCC") (class "Default")
      (node (ref "C1") (pin "1") (pinfunction "1_1") (pintype "passive"))
      (node (ref "C2") (pin "1") (pinfunction "1_1") (pintype "passive"))
      (node (ref "C3") (pin "1") (pinfunction "1_1") (pintype "passive"))
      (node (ref "C4") (pin "1") (pinfunction "1_1") (pintype "passive"))
      (node (ref "C5") (pin "1") (pinfunction "+_1") (pintype "passive"))
      (node (ref "C7") (pin "1") (pinfunction "1_1") (pintype "passive"))
      (node (ref "IC1") (pin "16") (pinfunction "VCC_16") (pintype "power_in"))
      (node (ref "IC2") (pin "16") (pinfunction "VCC_16") (pintype "power_in"))
      (node (ref "IC3") (pin "16") (pinfunction "VCC_16") (pintype "power_in"))
      (node (ref "IC4") (pin "16") (pinfunction "VCC_16") (pintype "power_in"))
      (node (ref "IC5") (pin "OUT") (pinfunction "OUT_OUT") (pintype "output"))
      (node (ref "JP1") (pin "1") (pinfunction "1_1") (pintype "passive"))
      (node (ref "JP2") (pin "1") (pinfunction "1_1") (pintype "passive"))
      (node (ref "R1") (pin "2") (pinfunction "2_2") (pintype "passive"))
    )
  )
)
